# tenere-controller-rev-A.net
KiCad netlist of a schematic drawn in EAGLE
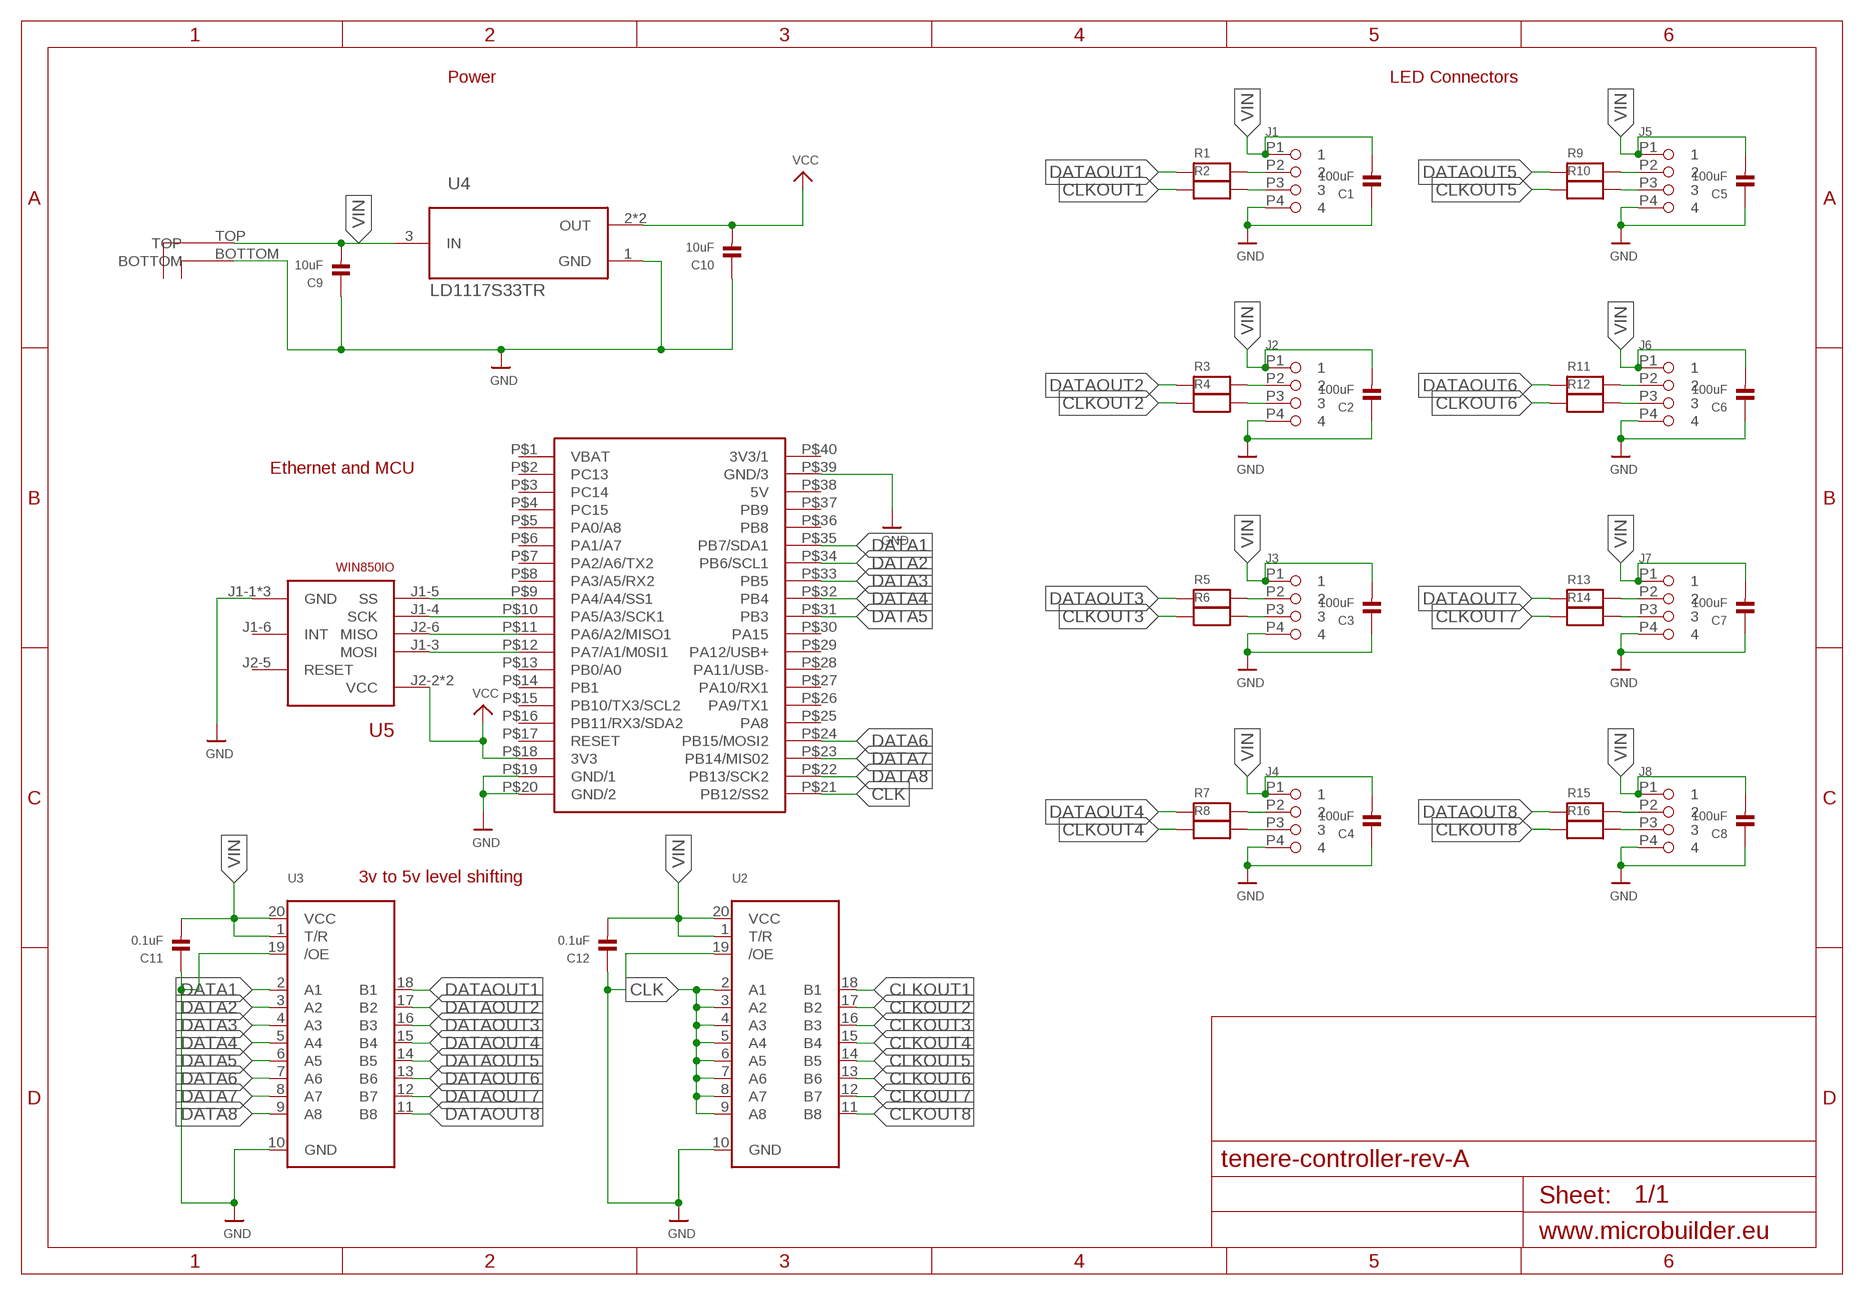
[diagram p0: schematic, sheet 1]

(export (version "E")
  (design (tool "Eeschema 10.0.6"))
  (components
    (comp (ref "C1")
      (value "100uF")
      (footprint "eagle-import:1206")
      (libsource (lib "eagle-import") (part "CAP_CERAMIC1206"))
    )
    (comp (ref "C2")
      (value "100uF")
      (footprint "eagle-import:1206")
      (libsource (lib "eagle-import") (part "CAP_CERAMIC1206"))
    )
    (comp (ref "C3")
      (value "100uF")
      (footprint "eagle-import:1206")
      (libsource (lib "eagle-import") (part "CAP_CERAMIC1206"))
    )
    (comp (ref "C4")
      (value "100uF")
      (footprint "eagle-import:1206")
      (libsource (lib "eagle-import") (part "CAP_CERAMIC1206"))
    )
    (comp (ref "C5")
      (value "100uF")
      (footprint "eagle-import:1206")
      (libsource (lib "eagle-import") (part "CAP_CERAMIC1206"))
    )
    (comp (ref "C6")
      (value "100uF")
      (footprint "eagle-import:1206")
      (libsource (lib "eagle-import") (part "CAP_CERAMIC1206"))
    )
    (comp (ref "C7")
      (value "100uF")
      (footprint "eagle-import:1206")
      (libsource (lib "eagle-import") (part "CAP_CERAMIC1206"))
    )
    (comp (ref "C8")
      (value "100uF")
      (footprint "eagle-import:1206")
      (libsource (lib "eagle-import") (part "CAP_CERAMIC1206"))
    )
    (comp (ref "C9")
      (value "10uF")
      (footprint "eagle-import:0603")
      (libsource (lib "eagle-import") (part "CAP_CERAMIC0603"))
    )
    (comp (ref "C10")
      (value "10uF")
      (footprint "eagle-import:0603")
      (libsource (lib "eagle-import") (part "CAP_CERAMIC0603"))
    )
    (comp (ref "C11")
      (value "0.1uF")
      (footprint "eagle-import:0603")
      (libsource (lib "eagle-import") (part "CAP_CERAMIC0603"))
    )
    (comp (ref "C12")
      (value "0.1uF")
      (footprint "eagle-import:0603")
      (libsource (lib "eagle-import") (part "CAP_CERAMIC0603"))
    )
    (comp (ref "J1")
      (value "JST-XH-4P-SODE")
      (footprint "eagle-import:JST-XH-BS4P")
      (libsource (lib "eagle-import") (part "JST-XH-4P-SODE"))
    )
    (comp (ref "J2")
      (value "JST-XH-4P-SODE")
      (footprint "eagle-import:JST-XH-BS4P")
      (libsource (lib "eagle-import") (part "JST-XH-4P-SODE"))
    )
    (comp (ref "J3")
      (value "JST-XH-4P-SODE")
      (footprint "eagle-import:JST-XH-BS4P")
      (libsource (lib "eagle-import") (part "JST-XH-4P-SODE"))
    )
    (comp (ref "J4")
      (value "JST-XH-4P-SODE")
      (footprint "eagle-import:JST-XH-BS4P")
      (libsource (lib "eagle-import") (part "JST-XH-4P-SODE"))
    )
    (comp (ref "J5")
      (value "JST-XH-4P-SODE")
      (footprint "eagle-import:JST-XH-BS4P")
      (libsource (lib "eagle-import") (part "JST-XH-4P-SODE"))
    )
    (comp (ref "J6")
      (value "JST-XH-4P-SODE")
      (footprint "eagle-import:JST-XH-BS4P")
      (libsource (lib "eagle-import") (part "JST-XH-4P-SODE"))
    )
    (comp (ref "J7")
      (value "JST-XH-4P-SODE")
      (footprint "eagle-import:JST-XH-BS4P")
      (libsource (lib "eagle-import") (part "JST-XH-4P-SODE"))
    )
    (comp (ref "J8")
      (value "JST-XH-4P-SODE")
      (footprint "eagle-import:JST-XH-BS4P")
      (libsource (lib "eagle-import") (part "JST-XH-4P-SODE"))
    )
    (comp (ref "J9")
      (value "POWERPOLE-2V")
      (footprint "eagle-import:POWERPOLE_STACKED")
      (libsource (lib "eagle-import") (part "POWERPOLE-2V"))
    )
    (comp (ref "R1")
      (value "RESISTOR0603")
      (footprint "eagle-import:0603")
      (libsource (lib "eagle-import") (part "RESISTOR0603"))
    )
    (comp (ref "R2")
      (value "RESISTOR0603")
      (footprint "eagle-import:0603")
      (libsource (lib "eagle-import") (part "RESISTOR0603"))
    )
    (comp (ref "R3")
      (value "RESISTOR0603")
      (footprint "eagle-import:0603")
      (libsource (lib "eagle-import") (part "RESISTOR0603"))
    )
    (comp (ref "R4")
      (value "RESISTOR0603")
      (footprint "eagle-import:0603")
      (libsource (lib "eagle-import") (part "RESISTOR0603"))
    )
    (comp (ref "R5")
      (value "RESISTOR0603")
      (footprint "eagle-import:0603")
      (libsource (lib "eagle-import") (part "RESISTOR0603"))
    )
    (comp (ref "R6")
      (value "RESISTOR0603")
      (footprint "eagle-import:0603")
      (libsource (lib "eagle-import") (part "RESISTOR0603"))
    )
    (comp (ref "R7")
      (value "RESISTOR0603")
      (footprint "eagle-import:0603")
      (libsource (lib "eagle-import") (part "RESISTOR0603"))
    )
    (comp (ref "R8")
      (value "RESISTOR0603")
      (footprint "eagle-import:0603")
      (libsource (lib "eagle-import") (part "RESISTOR0603"))
    )
    (comp (ref "R9")
      (value "RESISTOR0603")
      (footprint "eagle-import:0603")
      (libsource (lib "eagle-import") (part "RESISTOR0603"))
    )
    (comp (ref "R10")
      (value "RESISTOR0603")
      (footprint "eagle-import:0603")
      (libsource (lib "eagle-import") (part "RESISTOR0603"))
    )
    (comp (ref "R11")
      (value "RESISTOR0603")
      (footprint "eagle-import:0603")
      (libsource (lib "eagle-import") (part "RESISTOR0603"))
    )
    (comp (ref "R12")
      (value "RESISTOR0603")
      (footprint "eagle-import:0603")
      (libsource (lib "eagle-import") (part "RESISTOR0603"))
    )
    (comp (ref "R13")
      (value "RESISTOR0603")
      (footprint "eagle-import:0603")
      (libsource (lib "eagle-import") (part "RESISTOR0603"))
    )
    (comp (ref "R14")
      (value "RESISTOR0603")
      (footprint "eagle-import:0603")
      (libsource (lib "eagle-import") (part "RESISTOR0603"))
    )
    (comp (ref "R15")
      (value "RESISTOR0603")
      (footprint "eagle-import:0603")
      (libsource (lib "eagle-import") (part "RESISTOR0603"))
    )
    (comp (ref "R16")
      (value "RESISTOR0603")
      (footprint "eagle-import:0603")
      (libsource (lib "eagle-import") (part "RESISTOR0603"))
    )
    (comp (ref "U1")
      (value "BLUEPILL")
      (footprint "eagle-import:40-DIP-BLUE-PIL")
      (libsource (lib "eagle-import") (part "BLUEPILL"))
    )
    (comp (ref "U2")
      (value "74LCX245")
      (footprint "eagle-import:TSSOP20")
      (libsource (lib "eagle-import") (part "74LCX245"))
    )
    (comp (ref "U3")
      (value "74LCX245")
      (footprint "eagle-import:TSSOP20")
      (libsource (lib "eagle-import") (part "74LCX245"))
    )
    (comp (ref "U4")
      (value "LD1117S33TR")
      (footprint "eagle-import:LD1117S33TR_SOT230P700X180-4N")
      (fields (field (name "MANUFACTURER") "ST Microelectronics"))
      (libsource (lib "eagle-import") (part "LD1117S33TR"))
    )
    (comp (ref "U5")
      (value "WIN850IO")
      (footprint "eagle-import:WIZ850IO")
      (libsource (lib "eagle-import") (part "WIN850IO"))
    )
  )
  (nets
    (net (code "1") (name "CLK") (class "Default")
      (node (ref "U1") (pin "P$21") (pinfunction "PB12/SS2_P$21") (pintype "bidirectional"))
      (node (ref "U2") (pin "2") (pinfunction "A1_2") (pintype "bidirectional"))
      (node (ref "U2") (pin "3") (pinfunction "A2_3") (pintype "bidirectional"))
      (node (ref "U2") (pin "4") (pinfunction "A3_4") (pintype "bidirectional"))
      (node (ref "U2") (pin "5") (pinfunction "A4_5") (pintype "bidirectional"))
      (node (ref "U2") (pin "6") (pinfunction "A5_6") (pintype "bidirectional"))
      (node (ref "U2") (pin "7") (pinfunction "A6_7") (pintype "bidirectional"))
      (node (ref "U2") (pin "8") (pinfunction "A7_8") (pintype "bidirectional"))
      (node (ref "U2") (pin "9") (pinfunction "A8_9") (pintype "bidirectional"))
    )
    (net (code "2") (name "CLKOUT1") (class "Default")
      (node (ref "R2") (pin "1") (pinfunction "1_1") (pintype "passive"))
      (node (ref "U2") (pin "18") (pinfunction "B1_18") (pintype "bidirectional"))
    )
    (net (code "3") (name "CLKOUT2") (class "Default")
      (node (ref "R4") (pin "1") (pinfunction "1_1") (pintype "passive"))
      (node (ref "U2") (pin "17") (pinfunction "B2_17") (pintype "bidirectional"))
    )
    (net (code "4") (name "CLKOUT3") (class "Default")
      (node (ref "R6") (pin "1") (pinfunction "1_1") (pintype "passive"))
      (node (ref "U2") (pin "16") (pinfunction "B3_16") (pintype "bidirectional"))
    )
    (net (code "5") (name "CLKOUT4") (class "Default")
      (node (ref "R8") (pin "1") (pinfunction "1_1") (pintype "passive"))
      (node (ref "U2") (pin "15") (pinfunction "B4_15") (pintype "bidirectional"))
    )
    (net (code "6") (name "CLKOUT5") (class "Default")
      (node (ref "R10") (pin "1") (pinfunction "1_1") (pintype "passive"))
      (node (ref "U2") (pin "14") (pinfunction "B5_14") (pintype "bidirectional"))
    )
    (net (code "7") (name "CLKOUT6") (class "Default")
      (node (ref "R12") (pin "1") (pinfunction "1_1") (pintype "passive"))
      (node (ref "U2") (pin "13") (pinfunction "B6_13") (pintype "bidirectional"))
    )
    (net (code "8") (name "CLKOUT7") (class "Default")
      (node (ref "R14") (pin "1") (pinfunction "1_1") (pintype "passive"))
      (node (ref "U2") (pin "12") (pinfunction "B7_12") (pintype "bidirectional"))
    )
    (net (code "9") (name "CLKOUT8") (class "Default")
      (node (ref "R16") (pin "1") (pinfunction "1_1") (pintype "passive"))
      (node (ref "U2") (pin "11") (pinfunction "B8_11") (pintype "bidirectional"))
    )
    (net (code "10") (name "DATA1") (class "Default")
      (node (ref "U1") (pin "P$35") (pinfunction "PB7/SDA1_P$35") (pintype "bidirectional"))
      (node (ref "U3") (pin "2") (pinfunction "A1_2") (pintype "bidirectional"))
    )
    (net (code "11") (name "DATA2") (class "Default")
      (node (ref "U1") (pin "P$34") (pinfunction "PB6/SCL1_P$34") (pintype "bidirectional"))
      (node (ref "U3") (pin "3") (pinfunction "A2_3") (pintype "bidirectional"))
    )
    (net (code "12") (name "DATA3") (class "Default")
      (node (ref "U1") (pin "P$33") (pinfunction "PB5_P$33") (pintype "bidirectional"))
      (node (ref "U3") (pin "4") (pinfunction "A3_4") (pintype "bidirectional"))
    )
    (net (code "13") (name "DATA4") (class "Default")
      (node (ref "U1") (pin "P$32") (pinfunction "PB4_P$32") (pintype "bidirectional"))
      (node (ref "U3") (pin "5") (pinfunction "A4_5") (pintype "bidirectional"))
    )
    (net (code "14") (name "DATA5") (class "Default")
      (node (ref "U1") (pin "P$31") (pinfunction "PB3_P$31") (pintype "bidirectional"))
      (node (ref "U3") (pin "6") (pinfunction "A5_6") (pintype "bidirectional"))
    )
    (net (code "15") (name "DATA6") (class "Default")
      (node (ref "U1") (pin "P$24") (pinfunction "PB15/MOSI2_P$24") (pintype "bidirectional"))
      (node (ref "U3") (pin "7") (pinfunction "A6_7") (pintype "bidirectional"))
    )
    (net (code "16") (name "DATA7") (class "Default")
      (node (ref "U1") (pin "P$23") (pinfunction "PB14/MIS02_P$23") (pintype "bidirectional"))
      (node (ref "U3") (pin "8") (pinfunction "A7_8") (pintype "bidirectional"))
    )
    (net (code "17") (name "DATA8") (class "Default")
      (node (ref "U1") (pin "P$22") (pinfunction "PB13/SCK2_P$22") (pintype "bidirectional"))
      (node (ref "U3") (pin "9") (pinfunction "A8_9") (pintype "bidirectional"))
    )
    (net (code "18") (name "DATAOUT1") (class "Default")
      (node (ref "R1") (pin "1") (pinfunction "1_1") (pintype "passive"))
      (node (ref "U3") (pin "18") (pinfunction "B1_18") (pintype "bidirectional"))
    )
    (net (code "19") (name "DATAOUT2") (class "Default")
      (node (ref "R3") (pin "1") (pinfunction "1_1") (pintype "passive"))
      (node (ref "U3") (pin "17") (pinfunction "B2_17") (pintype "bidirectional"))
    )
    (net (code "20") (name "DATAOUT3") (class "Default")
      (node (ref "R5") (pin "1") (pinfunction "1_1") (pintype "passive"))
      (node (ref "U3") (pin "16") (pinfunction "B3_16") (pintype "bidirectional"))
    )
    (net (code "21") (name "DATAOUT4") (class "Default")
      (node (ref "R7") (pin "1") (pinfunction "1_1") (pintype "passive"))
      (node (ref "U3") (pin "15") (pinfunction "B4_15") (pintype "bidirectional"))
    )
    (net (code "22") (name "DATAOUT5") (class "Default")
      (node (ref "R9") (pin "1") (pinfunction "1_1") (pintype "passive"))
      (node (ref "U3") (pin "14") (pinfunction "B5_14") (pintype "bidirectional"))
    )
    (net (code "23") (name "DATAOUT6") (class "Default")
      (node (ref "R11") (pin "1") (pinfunction "1_1") (pintype "passive"))
      (node (ref "U3") (pin "13") (pinfunction "B6_13") (pintype "bidirectional"))
    )
    (net (code "24") (name "DATAOUT7") (class "Default")
      (node (ref "R13") (pin "1") (pinfunction "1_1") (pintype "passive"))
      (node (ref "U3") (pin "12") (pinfunction "B7_12") (pintype "bidirectional"))
    )
    (net (code "25") (name "DATAOUT8") (class "Default")
      (node (ref "R15") (pin "1") (pinfunction "1_1") (pintype "passive"))
      (node (ref "U3") (pin "11") (pinfunction "B8_11") (pintype "bidirectional"))
    )
    (net (code "26") (name "GND") (class "Default")
      (node (ref "C1") (pin "1") (pinfunction "P$1_1") (pintype "passive"))
      (node (ref "C10") (pin "1") (pinfunction "P$1_1") (pintype "passive"))
      (node (ref "C11") (pin "1") (pinfunction "P$1_1") (pintype "passive"))
      (node (ref "C12") (pin "1") (pinfunction "P$1_1") (pintype "passive"))
      (node (ref "C2") (pin "1") (pinfunction "P$1_1") (pintype "passive"))
      (node (ref "C3") (pin "1") (pinfunction "P$1_1") (pintype "passive"))
      (node (ref "C4") (pin "1") (pinfunction "P$1_1") (pintype "passive"))
      (node (ref "C5") (pin "1") (pinfunction "P$1_1") (pintype "passive"))
      (node (ref "C6") (pin "1") (pinfunction "P$1_1") (pintype "passive"))
      (node (ref "C7") (pin "1") (pinfunction "P$1_1") (pintype "passive"))
      (node (ref "C8") (pin "1") (pinfunction "P$1_1") (pintype "passive"))
      (node (ref "C9") (pin "1") (pinfunction "P$1_1") (pintype "passive"))
      (node (ref "J1") (pin "P4") (pinfunction "4_P4") (pintype "bidirectional"))
      (node (ref "J2") (pin "P4") (pinfunction "4_P4") (pintype "bidirectional"))
      (node (ref "J3") (pin "P4") (pinfunction "4_P4") (pintype "bidirectional"))
      (node (ref "J4") (pin "P4") (pinfunction "4_P4") (pintype "bidirectional"))
      (node (ref "J5") (pin "P4") (pinfunction "4_P4") (pintype "bidirectional"))
      (node (ref "J6") (pin "P4") (pinfunction "4_P4") (pintype "bidirectional"))
      (node (ref "J7") (pin "P4") (pinfunction "4_P4") (pintype "bidirectional"))
      (node (ref "J8") (pin "P4") (pinfunction "4_P4") (pintype "bidirectional"))
      (node (ref "J9") (pin "BOTTOM") (pinfunction "BOTTOM_BOTTOM") (pintype "bidirectional"))
      (node (ref "U1") (pin "P$19") (pinfunction "GND/1_P$19") (pintype "bidirectional"))
      (node (ref "U1") (pin "P$20") (pinfunction "GND/2_P$20") (pintype "bidirectional"))
      (node (ref "U1") (pin "P$39") (pinfunction "GND/3_P$39") (pintype "bidirectional"))
      (node (ref "U2") (pin "10") (pinfunction "GND_10") (pintype "bidirectional"))
      (node (ref "U2") (pin "19") (pinfunction "/OE_19") (pintype "bidirectional"))
      (node (ref "U3") (pin "10") (pinfunction "GND_10") (pintype "bidirectional"))
      (node (ref "U3") (pin "19") (pinfunction "/OE_19") (pintype "bidirectional"))
      (node (ref "U4") (pin "1") (pinfunction "GND_1") (pintype "power_in"))
      (node (ref "U5") (pin "J1-1") (pinfunction "GND_J1-1") (pintype "bidirectional"))
      (node (ref "U5") (pin "J1-2") (pinfunction "GND_J1-2") (pintype "bidirectional"))
      (node (ref "U5") (pin "J2-1") (pinfunction "GND_J2-1") (pintype "bidirectional"))
    )
    (net (code "27") (name "Net-(J1-2)") (class "Default")
      (node (ref "J1") (pin "P2") (pinfunction "2_P2") (pintype "bidirectional"))
      (node (ref "R1") (pin "2") (pinfunction "2_2") (pintype "passive"))
    )
    (net (code "28") (name "Net-(J1-3)") (class "Default")
      (node (ref "J1") (pin "P3") (pinfunction "3_P3") (pintype "bidirectional"))
      (node (ref "R2") (pin "2") (pinfunction "2_2") (pintype "passive"))
    )
    (net (code "29") (name "Net-(J2-2)") (class "Default")
      (node (ref "J2") (pin "P2") (pinfunction "2_P2") (pintype "bidirectional"))
      (node (ref "R3") (pin "2") (pinfunction "2_2") (pintype "passive"))
    )
    (net (code "30") (name "Net-(J2-3)") (class "Default")
      (node (ref "J2") (pin "P3") (pinfunction "3_P3") (pintype "bidirectional"))
      (node (ref "R4") (pin "2") (pinfunction "2_2") (pintype "passive"))
    )
    (net (code "31") (name "Net-(J3-2)") (class "Default")
      (node (ref "J3") (pin "P2") (pinfunction "2_P2") (pintype "bidirectional"))
      (node (ref "R5") (pin "2") (pinfunction "2_2") (pintype "passive"))
    )
    (net (code "32") (name "Net-(J3-3)") (class "Default")
      (node (ref "J3") (pin "P3") (pinfunction "3_P3") (pintype "bidirectional"))
      (node (ref "R6") (pin "2") (pinfunction "2_2") (pintype "passive"))
    )
    (net (code "33") (name "Net-(J4-2)") (class "Default")
      (node (ref "J4") (pin "P2") (pinfunction "2_P2") (pintype "bidirectional"))
      (node (ref "R7") (pin "2") (pinfunction "2_2") (pintype "passive"))
    )
    (net (code "34") (name "Net-(J4-3)") (class "Default")
      (node (ref "J4") (pin "P3") (pinfunction "3_P3") (pintype "bidirectional"))
      (node (ref "R8") (pin "2") (pinfunction "2_2") (pintype "passive"))
    )
    (net (code "35") (name "Net-(J5-2)") (class "Default")
      (node (ref "J5") (pin "P2") (pinfunction "2_P2") (pintype "bidirectional"))
      (node (ref "R9") (pin "2") (pinfunction "2_2") (pintype "passive"))
    )
    (net (code "36") (name "Net-(J5-3)") (class "Default")
      (node (ref "J5") (pin "P3") (pinfunction "3_P3") (pintype "bidirectional"))
      (node (ref "R10") (pin "2") (pinfunction "2_2") (pintype "passive"))
    )
    (net (code "37") (name "Net-(J6-2)") (class "Default")
      (node (ref "J6") (pin "P2") (pinfunction "2_P2") (pintype "bidirectional"))
      (node (ref "R11") (pin "2") (pinfunction "2_2") (pintype "passive"))
    )
    (net (code "38") (name "Net-(J6-3)") (class "Default")
      (node (ref "J6") (pin "P3") (pinfunction "3_P3") (pintype "bidirectional"))
      (node (ref "R12") (pin "2") (pinfunction "2_2") (pintype "passive"))
    )
    (net (code "39") (name "Net-(J7-2)") (class "Default")
      (node (ref "J7") (pin "P2") (pinfunction "2_P2") (pintype "bidirectional"))
      (node (ref "R13") (pin "2") (pinfunction "2_2") (pintype "passive"))
    )
    (net (code "40") (name "Net-(J7-3)") (class "Default")
      (node (ref "J7") (pin "P3") (pinfunction "3_P3") (pintype "bidirectional"))
      (node (ref "R14") (pin "2") (pinfunction "2_2") (pintype "passive"))
    )
    (net (code "41") (name "Net-(J8-2)") (class "Default")
      (node (ref "J8") (pin "P2") (pinfunction "2_P2") (pintype "bidirectional"))
      (node (ref "R15") (pin "2") (pinfunction "2_2") (pintype "passive"))
    )
    (net (code "42") (name "Net-(J8-3)") (class "Default")
      (node (ref "J8") (pin "P3") (pinfunction "3_P3") (pintype "bidirectional"))
      (node (ref "R16") (pin "2") (pinfunction "2_2") (pintype "passive"))
    )
    (net (code "43") (name "Net-(U1-PA4{slash}A4{slash}SS1)") (class "Default")
      (node (ref "U1") (pin "P$9") (pinfunction "PA4/A4/SS1_P$9") (pintype "bidirectional"))
      (node (ref "U5") (pin "J1-5") (pinfunction "SS_J1-5") (pintype "bidirectional"))
    )
    (net (code "44") (name "Net-(U1-PA5{slash}A3{slash}SCK1)") (class "Default")
      (node (ref "U1") (pin "P$10") (pinfunction "PA5/A3/SCK1_P$10") (pintype "bidirectional"))
      (node (ref "U5") (pin "J1-4") (pinfunction "SCK_J1-4") (pintype "bidirectional"))
    )
    (net (code "45") (name "Net-(U1-PA6{slash}A2{slash}MISO1)") (class "Default")
      (node (ref "U1") (pin "P$11") (pinfunction "PA6/A2/MISO1_P$11") (pintype "bidirectional"))
      (node (ref "U5") (pin "J2-6") (pinfunction "MISO_J2-6") (pintype "bidirectional"))
    )
    (net (code "46") (name "Net-(U1-PA7{slash}A1{slash}M0SI1)") (class "Default")
      (node (ref "U1") (pin "P$12") (pinfunction "PA7/A1/M0SI1_P$12") (pintype "bidirectional"))
      (node (ref "U5") (pin "J1-3") (pinfunction "MOSI_J1-3") (pintype "bidirectional"))
    )
    (net (code "47") (name "VCC") (class "Default")
      (node (ref "C10") (pin "2") (pinfunction "P$2_2") (pintype "passive"))
      (node (ref "U1") (pin "P$18") (pinfunction "3V3_P$18") (pintype "bidirectional"))
      (node (ref "U4") (pin "2") (pinfunction "OUT_2") (pintype "output"))
      (node (ref "U4") (pin "4") (pinfunction "OUT_4") (pintype "output"))
      (node (ref "U5") (pin "J2-2") (pinfunction "VCC_J2-2") (pintype "bidirectional"))
      (node (ref "U5") (pin "J2-3") (pinfunction "VCC_J2-3") (pintype "bidirectional"))
    )
    (net (code "48") (name "VIN") (class "Default")
      (node (ref "C1") (pin "2") (pinfunction "P$2_2") (pintype "passive"))
      (node (ref "C11") (pin "2") (pinfunction "P$2_2") (pintype "passive"))
      (node (ref "C12") (pin "2") (pinfunction "P$2_2") (pintype "passive"))
      (node (ref "C2") (pin "2") (pinfunction "P$2_2") (pintype "passive"))
      (node (ref "C3") (pin "2") (pinfunction "P$2_2") (pintype "passive"))
      (node (ref "C4") (pin "2") (pinfunction "P$2_2") (pintype "passive"))
      (node (ref "C5") (pin "2") (pinfunction "P$2_2") (pintype "passive"))
      (node (ref "C6") (pin "2") (pinfunction "P$2_2") (pintype "passive"))
      (node (ref "C7") (pin "2") (pinfunction "P$2_2") (pintype "passive"))
      (node (ref "C8") (pin "2") (pinfunction "P$2_2") (pintype "passive"))
      (node (ref "C9") (pin "2") (pinfunction "P$2_2") (pintype "passive"))
      (node (ref "J1") (pin "P1") (pinfunction "1_P1") (pintype "bidirectional"))
      (node (ref "J2") (pin "P1") (pinfunction "1_P1") (pintype "bidirectional"))
      (node (ref "J3") (pin "P1") (pinfunction "1_P1") (pintype "bidirectional"))
      (node (ref "J4") (pin "P1") (pinfunction "1_P1") (pintype "bidirectional"))
      (node (ref "J5") (pin "P1") (pinfunction "1_P1") (pintype "bidirectional"))
      (node (ref "J6") (pin "P1") (pinfunction "1_P1") (pintype "bidirectional"))
      (node (ref "J7") (pin "P1") (pinfunction "1_P1") (pintype "bidirectional"))
      (node (ref "J8") (pin "P1") (pinfunction "1_P1") (pintype "bidirectional"))
      (node (ref "J9") (pin "TOP") (pinfunction "TOP_TOP") (pintype "bidirectional"))
      (node (ref "U2") (pin "1") (pinfunction "T/R_1") (pintype "bidirectional"))
      (node (ref "U2") (pin "20") (pinfunction "VCC_20") (pintype "bidirectional"))
      (node (ref "U3") (pin "1") (pinfunction "T/R_1") (pintype "bidirectional"))
      (node (ref "U3") (pin "20") (pinfunction "VCC_20") (pintype "bidirectional"))
      (node (ref "U4") (pin "3") (pinfunction "IN_3") (pintype "input"))
    )
    (net (code "49") (name "unconnected-(U1-3V3{slash}1-PadP$40)") (class "Default")
      (node (ref "U1") (pin "P$40") (pinfunction "3V3/1_P$40") (pintype "bidirectional"))
    )
    (net (code "50") (name "unconnected-(U1-5V-PadP$38)") (class "Default")
      (node (ref "U1") (pin "P$38") (pinfunction "5V_P$38") (pintype "bidirectional"))
    )
    (net (code "51") (name "unconnected-(U1-PA0{slash}A8-PadP$5)") (class "Default")
      (node (ref "U1") (pin "P$5") (pinfunction "PA0/A8_P$5") (pintype "bidirectional"))
    )
    (net (code "52") (name "unconnected-(U1-PA1{slash}A7-PadP$6)") (class "Default")
      (node (ref "U1") (pin "P$6") (pinfunction "PA1/A7_P$6") (pintype "bidirectional"))
    )
    (net (code "53") (name "unconnected-(U1-PA2{slash}A6{slash}TX2-PadP$7)") (class "Default")
      (node (ref "U1") (pin "P$7") (pinfunction "PA2/A6/TX2_P$7") (pintype "bidirectional"))
    )
    (net (code "54") (name "unconnected-(U1-PA3{slash}A5{slash}RX2-PadP$8)") (class "Default")
      (node (ref "U1") (pin "P$8") (pinfunction "PA3/A5/RX2_P$8") (pintype "bidirectional"))
    )
    (net (code "55") (name "unconnected-(U1-PA8-PadP$25)") (class "Default")
      (node (ref "U1") (pin "P$25") (pinfunction "PA8_P$25") (pintype "bidirectional"))
    )
    (net (code "56") (name "unconnected-(U1-PA9{slash}TX1-PadP$26)") (class "Default")
      (node (ref "U1") (pin "P$26") (pinfunction "PA9/TX1_P$26") (pintype "bidirectional"))
    )
    (net (code "57") (name "unconnected-(U1-PA10{slash}RX1-PadP$27)") (class "Default")
      (node (ref "U1") (pin "P$27") (pinfunction "PA10/RX1_P$27") (pintype "bidirectional"))
    )
    (net (code "58") (name "unconnected-(U1-PA11{slash}USB--PadP$28)") (class "Default")
      (node (ref "U1") (pin "P$28") (pinfunction "PA11/USB-_P$28") (pintype "bidirectional"))
    )
    (net (code "59") (name "unconnected-(U1-PA12{slash}USB+-PadP$29)") (class "Default")
      (node (ref "U1") (pin "P$29") (pinfunction "PA12/USB+_P$29") (pintype "bidirectional"))
    )
    (net (code "60") (name "unconnected-(U1-PA15-PadP$30)") (class "Default")
      (node (ref "U1") (pin "P$30") (pinfunction "PA15_P$30") (pintype "bidirectional"))
    )
    (net (code "61") (name "unconnected-(U1-PB0{slash}A0-PadP$13)") (class "Default")
      (node (ref "U1") (pin "P$13") (pinfunction "PB0/A0_P$13") (pintype "bidirectional"))
    )
    (net (code "62") (name "unconnected-(U1-PB1-PadP$14)") (class "Default")
      (node (ref "U1") (pin "P$14") (pinfunction "PB1_P$14") (pintype "bidirectional"))
    )
    (net (code "63") (name "unconnected-(U1-PB8-PadP$36)") (class "Default")
      (node (ref "U1") (pin "P$36") (pinfunction "PB8_P$36") (pintype "bidirectional"))
    )
    (net (code "64") (name "unconnected-(U1-PB9-PadP$37)") (class "Default")
      (node (ref "U1") (pin "P$37") (pinfunction "PB9_P$37") (pintype "bidirectional"))
    )
    (net (code "65") (name "unconnected-(U1-PB10{slash}TX3{slash}SCL2-PadP$15)") (class "Default")
      (node (ref "U1") (pin "P$15") (pinfunction "PB10/TX3/SCL2_P$15") (pintype "bidirectional"))
    )
    (net (code "66") (name "unconnected-(U1-PB11{slash}RX3{slash}SDA2-PadP$16)") (class "Default")
      (node (ref "U1") (pin "P$16") (pinfunction "PB11/RX3/SDA2_P$16") (pintype "bidirectional"))
    )
    (net (code "67") (name "unconnected-(U1-PC13-PadP$2)") (class "Default")
      (node (ref "U1") (pin "P$2") (pinfunction "PC13_P$2") (pintype "bidirectional"))
    )
    (net (code "68") (name "unconnected-(U1-PC14-PadP$3)") (class "Default")
      (node (ref "U1") (pin "P$3") (pinfunction "PC14_P$3") (pintype "bidirectional"))
    )
    (net (code "69") (name "unconnected-(U1-PC15-PadP$4)") (class "Default")
      (node (ref "U1") (pin "P$4") (pinfunction "PC15_P$4") (pintype "bidirectional"))
    )
    (net (code "70") (name "unconnected-(U1-RESET-PadP$17)") (class "Default")
      (node (ref "U1") (pin "P$17") (pinfunction "RESET_P$17") (pintype "bidirectional"))
    )
    (net (code "71") (name "unconnected-(U1-VBAT-PadP$1)") (class "Default")
      (node (ref "U1") (pin "P$1") (pinfunction "VBAT_P$1") (pintype "bidirectional"))
    )
    (net (code "72") (name "unconnected-(U5-INT-PadJ1-6)") (class "Default")
      (node (ref "U5") (pin "J1-6") (pinfunction "INT_J1-6") (pintype "bidirectional"))
    )
    (net (code "73") (name "unconnected-(U5-RESET-PadJ2-5)") (class "Default")
      (node (ref "U5") (pin "J2-5") (pinfunction "RESET_J2-5") (pintype "bidirectional"))
    )
  )
)
